# 03_POWER_PROTECTION_MONITORING.net
KiCad netlist of a schematic drawn in Altium Designer
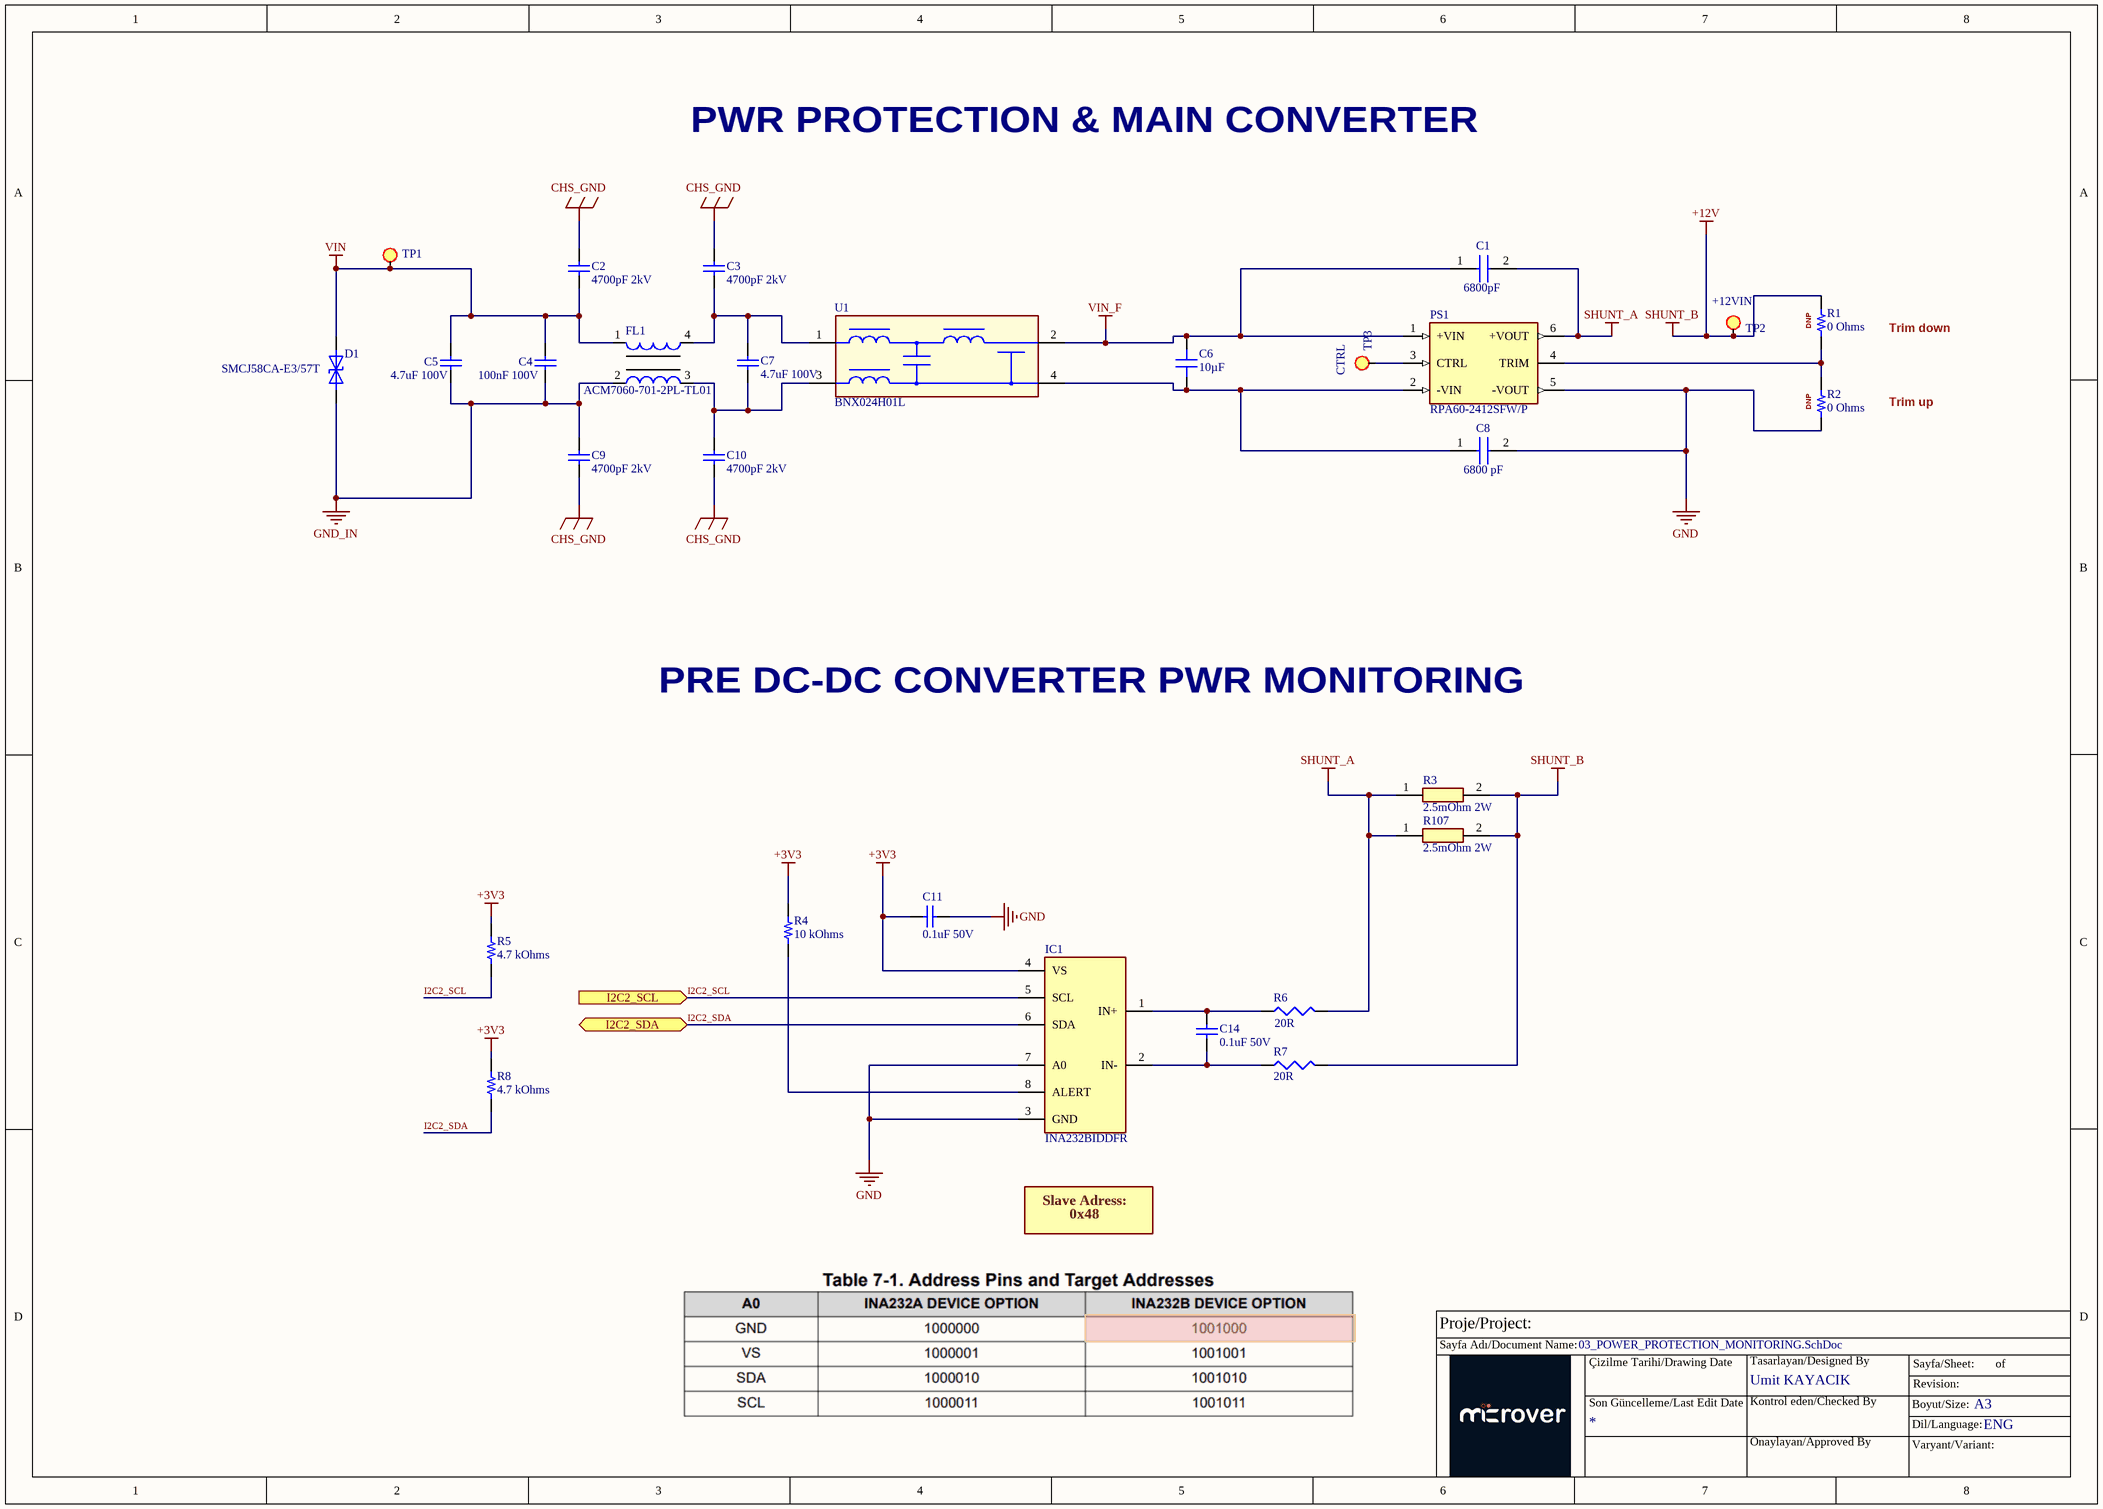
[diagram p0: 03_POWER_PROTECTION_MONITORING.SchDoc]

(export (version "E")
  (design (tool "Eeschema 10.0.6"))
  (components
    (comp (ref "C1")
      (value "6800pF")
      (footprint "CAPC3225X280N")
      (description "CAP CER SMD 1210 6800PF 20% 2KV")
      (fields (field (name "MANUFACTURER_PART_NUMBER") "C1210C682MGRAC7800"))
      (libsource (lib "*") (part "C1210C682MGRAC7800"))
    )
    (comp (ref "C2")
      (value "4700pF 2kV")
      (footprint "CAP1812")
      (description "2kV 4.7nF X7R ±10% 1812 Multilayer Ceramic Capacitors MLCC - SMD/SMT ROHS")
      (fields
        (field (name "MANUFACTURER PART NUMBER") "202S43W472KV4E")
        (field (name "LCSC PART NUMBER") "C167436")
      )
      (libsource (lib "HW_HOLLAND_NCDM_MONITOR_R1") (part "CAP1812_4700PF_2KV"))
    )
    (comp (ref "C3")
      (value "4700pF 2kV")
      (footprint "CAP1812")
      (description "2kV 4.7nF X7R ±10% 1812 Multilayer Ceramic Capacitors MLCC - SMD/SMT ROHS")
      (fields
        (field (name "MANUFACTURER PART NUMBER") "202S43W472KV4E")
        (field (name "LCSC PART NUMBER") "C167436")
      )
      (libsource (lib "HW_HOLLAND_NCDM_MONITOR_R1") (part "CAP1812_4700PF_2KV"))
    )
    (comp (ref "C4")
      (value "100nF 100V")
      (footprint "SMC0805")
      (description "0.1 µF ±10% 100V Ceramic Capacitor X7R 0805 (2012 Metric)")
      (fields
        (field (name "MANUFACTURER PART NUMBER") "CL21B104KCFNNNE")
        (field (name "LCSC PART NUMBER") "C28233")
      )
      (libsource (lib "HW_HOLLAND_NCDM_MONITOR_R1") (part "CAP0805_100nF_100V"))
    )
    (comp (ref "C5")
      (value "4.7uF 100V")
      (footprint "CAP1210")
      (description "4.7 µF ±10% 100V Ceramic Capacitor X7S 1210 (3225 Metric)")
      (fields
        (field (name "MANUFACTURER PART NUMBER") "CL32Y475KCIVPNE")
        (field (name "LCSC PART NUMBER") "C2803397")
      )
      (libsource (lib "HW_HOLLAND_NCDM_MONITOR_R1") (part "CAP1210_4.7UF_100V"))
    )
    (comp (ref "C6")
      (value "10µF")
      (footprint "CAP 1206_3216 - 1.8MM")
      (description "CAP CER 10UF 50V X5R 1206")
      (fields (field (name "PART NUMBER") "12065D106KAT2A") (field (name "MANUFACTURER") "AVX Corporation"))
      (libsource (lib "Celestial Altium Library - altium_library") (part "Capacitor"))
    )
    (comp (ref "C7")
      (value "4.7uF 100V")
      (footprint "CAP1210")
      (description "4.7 µF ±10% 100V Ceramic Capacitor X7S 1210 (3225 Metric)")
      (fields
        (field (name "MANUFACTURER PART NUMBER") "CL32Y475KCIVPNE")
        (field (name "LCSC PART NUMBER") "C2803397")
      )
      (libsource (lib "HW_HOLLAND_NCDM_MONITOR_R1") (part "CAP1210_4.7UF_100V"))
    )
    (comp (ref "C8")
      (value "6800 pF")
      (footprint "CAPC3225X280N")
      (description "Capacitor")
      (fields (field (name "MANUFACTURER_PART_NUMBER") "C1210C682MGRAC7800"))
      (libsource (lib "*") (part "C1210C682MGRAC7800"))
    )
    (comp (ref "C9")
      (value "4700pF 2kV")
      (footprint "CAP1812")
      (description "2kV 4.7nF X7R ±10% 1812 Multilayer Ceramic Capacitors MLCC - SMD/SMT ROHS")
      (fields
        (field (name "MANUFACTURER PART NUMBER") "202S43W472KV4E")
        (field (name "LCSC PART NUMBER") "C167436")
      )
      (libsource (lib "HW_HOLLAND_NCDM_MONITOR_R1") (part "CAP1812_4700PF_2KV"))
    )
    (comp (ref "C10")
      (value "4700pF 2kV")
      (footprint "CAP1812")
      (description "2kV 4.7nF X7R ±10% 1812 Multilayer Ceramic Capacitors MLCC - SMD/SMT ROHS")
      (fields
        (field (name "MANUFACTURER PART NUMBER") "202S43W472KV4E")
        (field (name "LCSC PART NUMBER") "C167436")
      )
      (libsource (lib "HW_HOLLAND_NCDM_MONITOR_R1") (part "CAP1812_4700PF_2KV"))
    )
    (comp (ref "C11")
      (value "0.1uF 50V")
      (footprint "SMC0603")
      (description "0.1 µF ±10% 50V Ceramic Capacitor X7R 0603 (1608 Metric)")
      (fields
        (field (name "MANUFACTURER PART NUMBER") "CL10B104KB8NNNL")
        (field (name "LCSC PART NUMBER") "C1591")
      )
      (libsource (lib "HW_HOLLAND_NCDM_MONITOR_R1") (part "CAP0603_0.1UF_50V"))
    )
    (comp (ref "C14")
      (value "0.1uF 50V")
      (footprint "SMC0603")
      (description "0.1 µF ±10% 50V Ceramic Capacitor X7R 0603 (1608 Metric)")
      (fields
        (field (name "MANUFACTURER PART NUMBER") "CL10B104KB8NNNL")
        (field (name "LCSC PART NUMBER") "C1591")
      )
      (libsource (lib "HW_HOLLAND_NCDM_MONITOR_R1") (part "CAP0603_0.1UF_50V"))
    )
    (comp (ref "D1")
      (value "SMCJ58CA-E3/57T")
      (footprint "DIOM7959X262N")
      (description "TransZorb 1500 W 58 V 93.6 Vcl Bi-Directional SMT TVS Diode - DO-214AB")
      (fields (field (name "MANUFACTURER") "Vishay Semiconductors"))
      (libsource (lib "HW_HOLLAND_NCDM_MONITOR_R1") (part "SMCJ58CA-E3/57T"))
    )
    (comp (ref "FL1")
      (value "CMC 4A 2LN 700 OHM SMD")
      (footprint "TDK_0_MFG")
      (description "2 Line Common Mode Choke Surface Mount 700 Ohms @ 100 MHz 4A DCR 15mOhm")
      (fields
        (field (name "LCSC MANUFACTURER PART NUMBER") "ACM7060-701-2PL-TL01")
        (field (name "LCSC PART NUMBER") "C78246")
        (field (name "MANUFACTURER PART NUMBER") "ACM7060-701-2PL-TL01")
      )
      (libsource (lib "HW_HOLLAND_NCDM_MONITOR_R1") (part "ACM7060-701-2PL-TL01"))
    )
    (comp (ref "IC1")
      (value "INA232BIDDFR")
      (footprint "SOT65P280X110-8N")
      (description "48-V, 16-bit high-precision I²C output digital power monitor with alert 8-SOT-23-THIN -40 to 125")
      (fields (field (name "MANUFACTURER") "Texas Instruments"))
      (libsource (lib "HW_HOLLAND_NCDM_MONITOR_R1") (part "INA232BIDDFR"))
    )
    (comp (ref "PS1")
      (value "RPA60-2412SFW/P")
      (footprint "CONV_RPA60-2412SFW/P")
      (description "60W DC/DC-Converter 'POWERLINE' 2 x1 1.5kV reg 4: ; V. In: 9-36; V. Out: 12; mA. Out: 5000")
      (fields (field (name "MANUFACTURER") "Recom"))
      (libsource (lib "HW_HOLLAND_NCDM_MONITOR_R1") (part "RPA60-2412SFW/P"))
    )
    (comp (ref "R1")
      (value "0 Ohms")
      (footprint "RES 0402_1005")
      (description "RES 0 OHM JUMPER 1/8W 0402")
      (fields
        (field (name "PART NUMBER") "HCJ0402ZT0R00")
        (field (name "MANUFACTURER") "Stackpole Electronics Inc")
      )
      (libsource (lib "Celestial Altium Library - altium_library") (part "Resistor"))
    )
    (comp (ref "R2")
      (value "0 Ohms")
      (footprint "RES 0402_1005")
      (description "RES 0 OHM JUMPER 1/8W 0402")
      (fields
        (field (name "PART NUMBER") "HCJ0402ZT0R00")
        (field (name "MANUFACTURER") "Stackpole Electronics Inc")
      )
      (libsource (lib "Celestial Altium Library - altium_library") (part "Resistor"))
    )
    (comp (ref "R3")
      (value "2.5mOhm 2W")
      (footprint "SamacSys:RESC5125X89N")
      (description "Resistor")
      (fields (field (name "MANUFACTURER_PART_NUMBER") "WSLP20102L500FEA"))
      (libsource (lib "*") (part "WSLP20102L500FEA"))
    )
    (comp (ref "R4")
      (value "10 kOhms")
      (footprint "RES 0402_1005")
      (description "RES 10K OHM 0.1% 1/10W 0402")
      (fields
        (field (name "PART NUMBER") "RP73PF1E10KBTD")
        (field (name "MANUFACTURER") "TE Connectivity Passive Product")
      )
      (libsource (lib "Celestial Altium Library - altium_library") (part "Resistor"))
    )
    (comp (ref "R5")
      (value "4.7 kOhms")
      (footprint "RES 0603_1608")
      (description "RES 4.7K OHM 0.1% 1/10W 0603")
      (fields
        (field (name "PART NUMBER") "RN73R1JTTD4701B25")
        (field (name "MANUFACTURER") "KOA Speer Electronics, Inc.")
      )
      (libsource (lib "Celestial Altium Library - altium_library") (part "Resistor"))
    )
    (comp (ref "R6")
      (value "20R")
      (footprint "RES0603")
      (description "20 Ohms ±1% 0.1W, 1/10W Chip Resistor 0603 (1608 Metric) Automotive AEC-Q200 Thick Film")
      (fields
        (field (name "MANUFACTURER PART NUMBER") "RMCF0603FT20R0")
        (field (name "LCSC MANUFACTURER PART NUMBER") "WR06X20R0FTL")
      )
      (libsource (lib "SCISONIC_CHARGER_V2.0") (part "RES0603_20R_%1"))
    )
    (comp (ref "R7")
      (value "20R")
      (footprint "RES0603")
      (description "20 Ohms ±1% 0.1W, 1/10W Chip Resistor 0603 (1608 Metric) Automotive AEC-Q200 Thick Film")
      (fields
        (field (name "MANUFACTURER PART NUMBER") "RMCF0603FT20R0")
        (field (name "LCSC MANUFACTURER PART NUMBER") "WR06X20R0FTL")
      )
      (libsource (lib "SCISONIC_CHARGER_V2.0") (part "RES0603_20R_%1"))
    )
    (comp (ref "R8")
      (value "4.7 kOhms")
      (footprint "RES 0603_1608")
      (description "RES 4.7K OHM 0.1% 1/10W 0603")
      (fields
        (field (name "PART NUMBER") "RN73R1JTTD4701B25")
        (field (name "MANUFACTURER") "KOA Speer Electronics, Inc.")
      )
      (libsource (lib "Celestial Altium Library - altium_library") (part "Resistor"))
    )
    (comp (ref "R107")
      (value "2.5mOhm 2W")
      (footprint "SamacSys:RESC5125X89N")
      (description "Resistor")
      (fields (field (name "MANUFACTURER_PART_NUMBER") "WSLP20102L500FEA"))
      (libsource (lib "*") (part "WSLP20102L500FEA"))
    )
    (comp (ref "TP1")
      (value "VIN")
      (footprint "TEST_POINT_SMD")
      (libsource (lib "HW_HOLLAND_NCDM_MONITOR_R1") (part "TP"))
    )
    (comp (ref "TP2")
      (value "+12VIN")
      (footprint "TEST_POINT_SMD")
      (libsource (lib "HW_HOLLAND_NCDM_MONITOR_R1") (part "TP"))
    )
    (comp (ref "TP3")
      (value "CTRL")
      (footprint "TEST_POINT_SMD")
      (libsource (lib "HW_HOLLAND_NCDM_MONITOR_R1") (part "TP"))
    )
    (comp (ref "U1")
      (value "FILTER LC 4.7UF SMD")
      (footprint "Murata_BNX02_MFG")
      (description "LC EMI Filter 5th Order Low Pass 2 Channel C = 4.7µF 20 A 4-SMD, No Lead")
      (fields
        (field (name "LCSC MANUFACTURER PART NUMBER") "BNX024H01L")
        (field (name "LCSC PART NUMBER") "C124739")
        (field (name "MANUFACTURER PART NUMBER") "BNX024H01L")
      )
      (libsource (lib "HW_HOLLAND_NCDM_MONITOR_R1") (part "BNX024H01L"))
    )
  )
  (nets
    (net (code "1") (name "+3V3") (class "Default")
      (node (ref "C11") (pin "1") (pinfunction "1_1") (pintype "passive"))
      (node (ref "IC1") (pin "4") (pinfunction "VS_4") (pintype "passive"))
      (node (ref "R4") (pin "2") (pinfunction "2_2") (pintype "passive"))
      (node (ref "R5") (pin "2") (pinfunction "2_2") (pintype "passive"))
      (node (ref "R8") (pin "2") (pinfunction "2_2") (pintype "passive"))
    )
    (net (code "2") (name "+12V") (class "Default")
      (node (ref "R1") (pin "2") (pinfunction "2_2") (pintype "passive"))
      (node (ref "R107") (pin "2") (pinfunction "2_2") (pintype "passive"))
      (node (ref "R3") (pin "2") (pinfunction "2_2") (pintype "passive"))
      (node (ref "R7") (pin "2") (pinfunction "2_2") (pintype "passive"))
      (node (ref "TP2") (pin "1") (pinfunction "TP_1") (pintype "passive"))
    )
    (net (code "3") (name "/I2C2_SCL") (class "Default")
      (node (ref "IC1") (pin "5") (pinfunction "SCL_5") (pintype "passive"))
      (node (ref "R5") (pin "1") (pinfunction "1_1") (pintype "passive"))
    )
    (net (code "4") (name "/I2C2_SDA") (class "Default")
      (node (ref "IC1") (pin "6") (pinfunction "SDA_6") (pintype "passive"))
      (node (ref "R8") (pin "1") (pinfunction "1_1") (pintype "passive"))
    )
    (net (code "5") (name "CHS_GND") (class "Default")
      (node (ref "C10") (pin "1") (pinfunction "1_1") (pintype "passive"))
      (node (ref "C2") (pin "2") (pinfunction "2_2") (pintype "passive"))
      (node (ref "C3") (pin "2") (pinfunction "2_2") (pintype "passive"))
      (node (ref "C9") (pin "1") (pinfunction "1_1") (pintype "passive"))
    )
    (net (code "6") (name "GND") (class "Default")
      (node (ref "C11") (pin "2") (pinfunction "2_2") (pintype "passive"))
      (node (ref "C8") (pin "2") (pinfunction "2_2") (pintype "passive"))
      (node (ref "IC1") (pin "3") (pinfunction "GND_3") (pintype "passive"))
      (node (ref "IC1") (pin "7") (pinfunction "A0_7") (pintype "passive"))
      (node (ref "PS1") (pin "5") (pinfunction "-VOUT_5") (pintype "output"))
      (node (ref "R2") (pin "1") (pinfunction "1_1") (pintype "passive"))
    )
    (net (code "7") (name "GND_IN") (class "Default")
      (node (ref "C4") (pin "1") (pinfunction "1_1") (pintype "passive"))
      (node (ref "C5") (pin "1") (pinfunction "1_1") (pintype "passive"))
      (node (ref "C9") (pin "2") (pinfunction "2_2") (pintype "passive"))
      (node (ref "D1") (pin "1") (pinfunction "1_1") (pintype "passive"))
      (node (ref "FL1") (pin "2") (pinfunction "2_2") (pintype "passive"))
    )
    (net (code "8") (name "Net-(IC1-ALERT)") (class "Default")
      (node (ref "IC1") (pin "8") (pinfunction "ALERT_8") (pintype "passive"))
      (node (ref "R4") (pin "1") (pinfunction "1_1") (pintype "passive"))
    )
    (net (code "9") (name "Net-(IC1-IN+)") (class "Default")
      (node (ref "C14") (pin "2") (pinfunction "2_2") (pintype "passive"))
      (node (ref "IC1") (pin "1") (pinfunction "IN+_1") (pintype "passive"))
      (node (ref "R6") (pin "1") (pinfunction "1_1") (pintype "passive"))
    )
    (net (code "10") (name "Net-(IC1-IN-)") (class "Default")
      (node (ref "C14") (pin "1") (pinfunction "1_1") (pintype "passive"))
      (node (ref "IC1") (pin "2") (pinfunction "IN-_2") (pintype "passive"))
      (node (ref "R7") (pin "1") (pinfunction "1_1") (pintype "passive"))
    )
    (net (code "11") (name "Net-(PS1--VIN)") (class "Default")
      (node (ref "C6") (pin "1") (pinfunction "1_1") (pintype "passive"))
      (node (ref "C8") (pin "1") (pinfunction "1_1") (pintype "passive"))
      (node (ref "PS1") (pin "2") (pinfunction "-VIN_2") (pintype "input"))
      (node (ref "U1") (pin "4") (pinfunction "CG_4") (pintype "passive"))
    )
    (net (code "12") (name "Net-(PS1-CTRL)") (class "Default")
      (node (ref "PS1") (pin "3") (pinfunction "CTRL_3") (pintype "input"))
      (node (ref "TP3") (pin "1") (pinfunction "TP_1") (pintype "passive"))
    )
    (net (code "13") (name "Net-(PS1-TRIM)") (class "Default")
      (node (ref "PS1") (pin "4") (pinfunction "TRIM_4") (pintype "passive"))
      (node (ref "R1") (pin "1") (pinfunction "1_1") (pintype "passive"))
      (node (ref "R2") (pin "2") (pinfunction "2_2") (pintype "passive"))
    )
    (net (code "14") (name "Net-(U1-B)") (class "Default")
      (node (ref "C3") (pin "1") (pinfunction "1_1") (pintype "passive"))
      (node (ref "C7") (pin "2") (pinfunction "2_2") (pintype "passive"))
      (node (ref "FL1") (pin "4") (pinfunction "4_4") (pintype "passive"))
      (node (ref "U1") (pin "1") (pinfunction "B_1") (pintype "passive"))
    )
    (net (code "15") (name "Net-(U1-PSG)") (class "Default")
      (node (ref "C10") (pin "2") (pinfunction "2_2") (pintype "passive"))
      (node (ref "C7") (pin "1") (pinfunction "1_1") (pintype "passive"))
      (node (ref "FL1") (pin "3") (pinfunction "3_3") (pintype "passive"))
      (node (ref "U1") (pin "3") (pinfunction "PSG_3") (pintype "passive"))
    )
    (net (code "16") (name "SHUNT_A") (class "Default")
      (node (ref "C1") (pin "2") (pinfunction "2_2") (pintype "passive"))
      (node (ref "PS1") (pin "6") (pinfunction "+VOUT_6") (pintype "output"))
      (node (ref "R107") (pin "1") (pinfunction "1_1") (pintype "passive"))
      (node (ref "R3") (pin "1") (pinfunction "1_1") (pintype "passive"))
      (node (ref "R6") (pin "2") (pinfunction "2_2") (pintype "passive"))
    )
    (net (code "17") (name "VIN") (class "Default")
      (node (ref "C2") (pin "1") (pinfunction "1_1") (pintype "passive"))
      (node (ref "C4") (pin "2") (pinfunction "2_2") (pintype "passive"))
      (node (ref "C5") (pin "2") (pinfunction "2_2") (pintype "passive"))
      (node (ref "D1") (pin "2") (pinfunction "2_2") (pintype "passive"))
      (node (ref "FL1") (pin "1") (pinfunction "1_1") (pintype "passive"))
      (node (ref "TP1") (pin "1") (pinfunction "TP_1") (pintype "passive"))
    )
    (net (code "18") (name "VIN_F") (class "Default")
      (node (ref "C1") (pin "1") (pinfunction "1_1") (pintype "passive"))
      (node (ref "C6") (pin "2") (pinfunction "2_2") (pintype "passive"))
      (node (ref "PS1") (pin "1") (pinfunction "+VIN_1") (pintype "input"))
      (node (ref "U1") (pin "2") (pinfunction "CB_2") (pintype "passive"))
    )
  )
)
